# SCH_Personal-Card_2024-08-31.net
KiCad netlist of a schematic drawn in EasyEDA
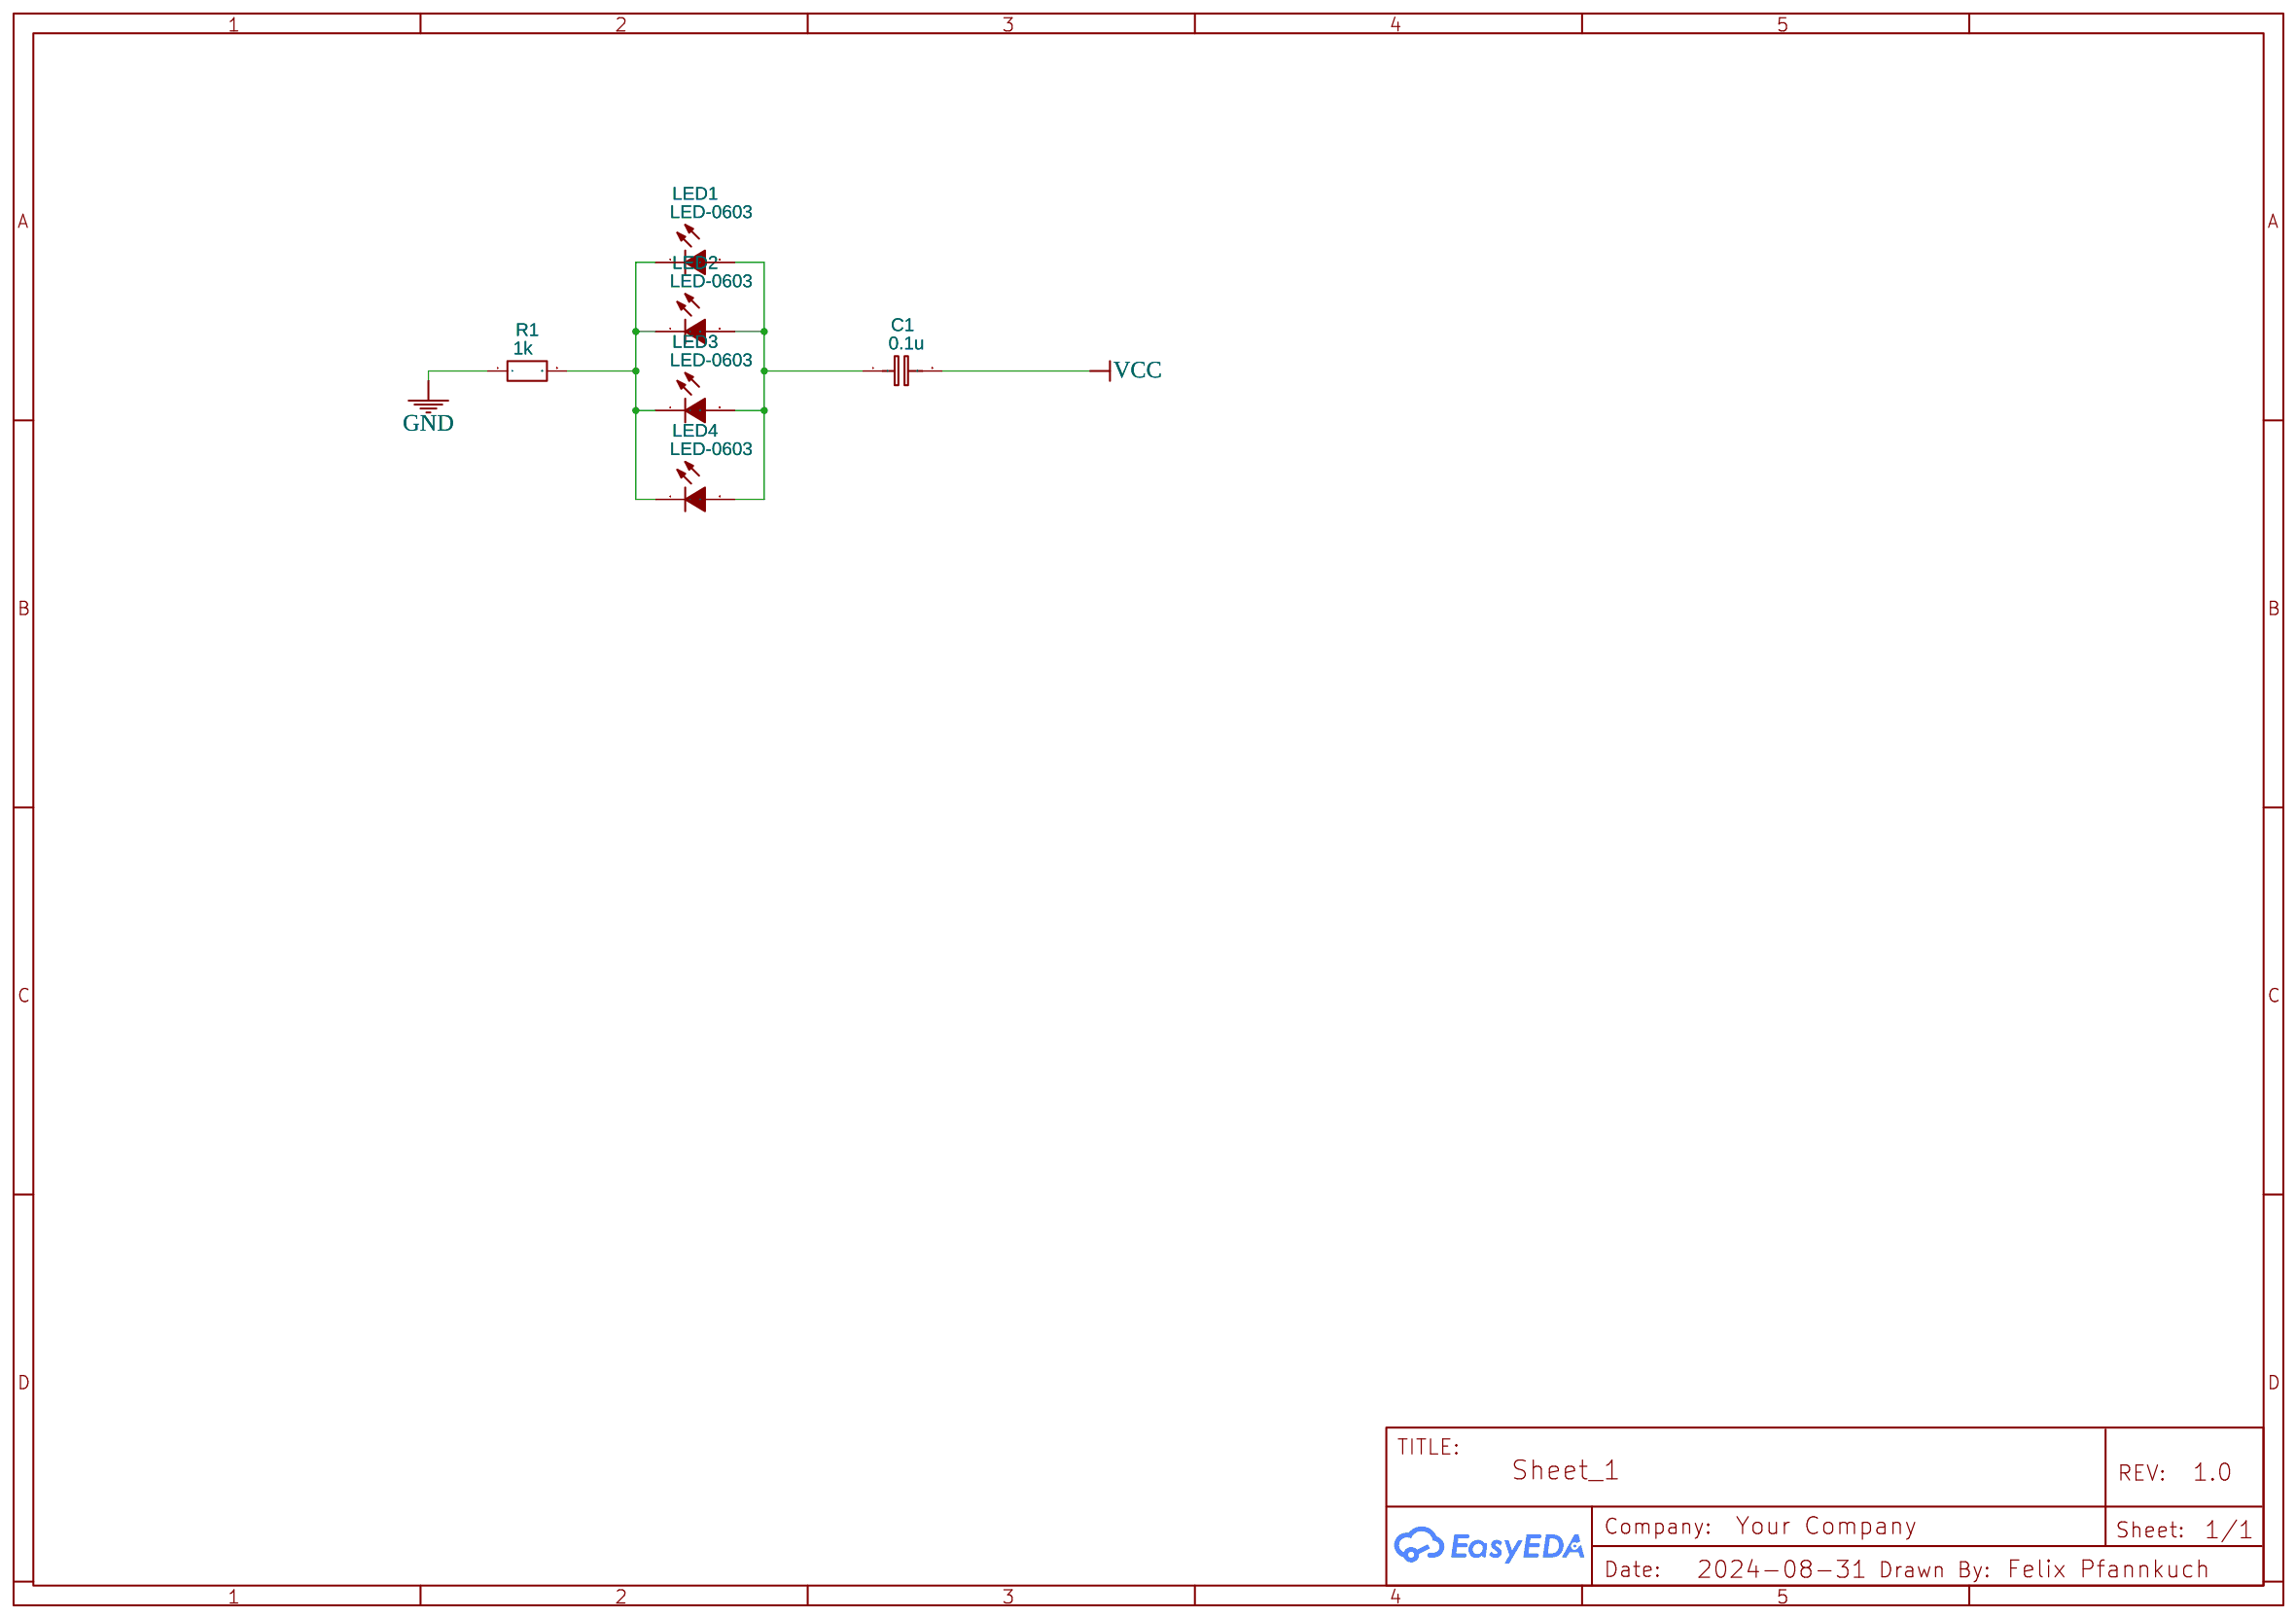
[diagram p0: schematic sheet]

(export (version "E")
  (design (tool "Eeschema 10.0.6"))
  (components
    (comp (ref "C1") (value "0.1u") (libsource (lib "") (part "C_0603_EU")))
    (comp (ref "LED1") (value "LED-0603") (libsource (lib "") (part "LED-0603")))
    (comp (ref "LED2") (value "LED-0603") (libsource (lib "") (part "LED-0603")))
    (comp (ref "LED3") (value "LED-0603") (libsource (lib "") (part "LED-0603")))
    (comp (ref "LED4") (value "LED-0603") (libsource (lib "") (part "LED-0603")))
    (comp (ref "R1") (value "1k") (libsource (lib "") (part "R_0603_EU")))
  )
  (nets
    (net (code "1") (name "GND") (class "Default")
      (node (ref "R1") (pin "1") (pinfunction "1_1") (pintype "unspecified"))
    )
    (net (code "2") (name "Net-(LED1-+)") (class "Default")
      (node (ref "C1") (pin "1") (pinfunction "1_1") (pintype "unspecified"))
      (node (ref "LED1") (pin "2") (pinfunction "+_2") (pintype "input"))
      (node (ref "LED2") (pin "2") (pinfunction "+_2") (pintype "input"))
      (node (ref "LED3") (pin "2") (pinfunction "+_2") (pintype "input"))
      (node (ref "LED4") (pin "2") (pinfunction "+_2") (pintype "input"))
    )
    (net (code "3") (name "Net-(LED1--)") (class "Default")
      (node (ref "LED1") (pin "1") (pinfunction "-_1") (pintype "input"))
      (node (ref "LED2") (pin "1") (pinfunction "-_1") (pintype "input"))
      (node (ref "LED3") (pin "1") (pinfunction "-_1") (pintype "input"))
      (node (ref "LED4") (pin "1") (pinfunction "-_1") (pintype "input"))
      (node (ref "R1") (pin "2") (pinfunction "2_2") (pintype "unspecified"))
    )
    (net (code "4") (name "VCC") (class "Default")
      (node (ref "C1") (pin "2") (pinfunction "2_2") (pintype "unspecified"))
    )
  )
)
